# Sch.net
KiCad netlist of a schematic drawn in Altium Designer
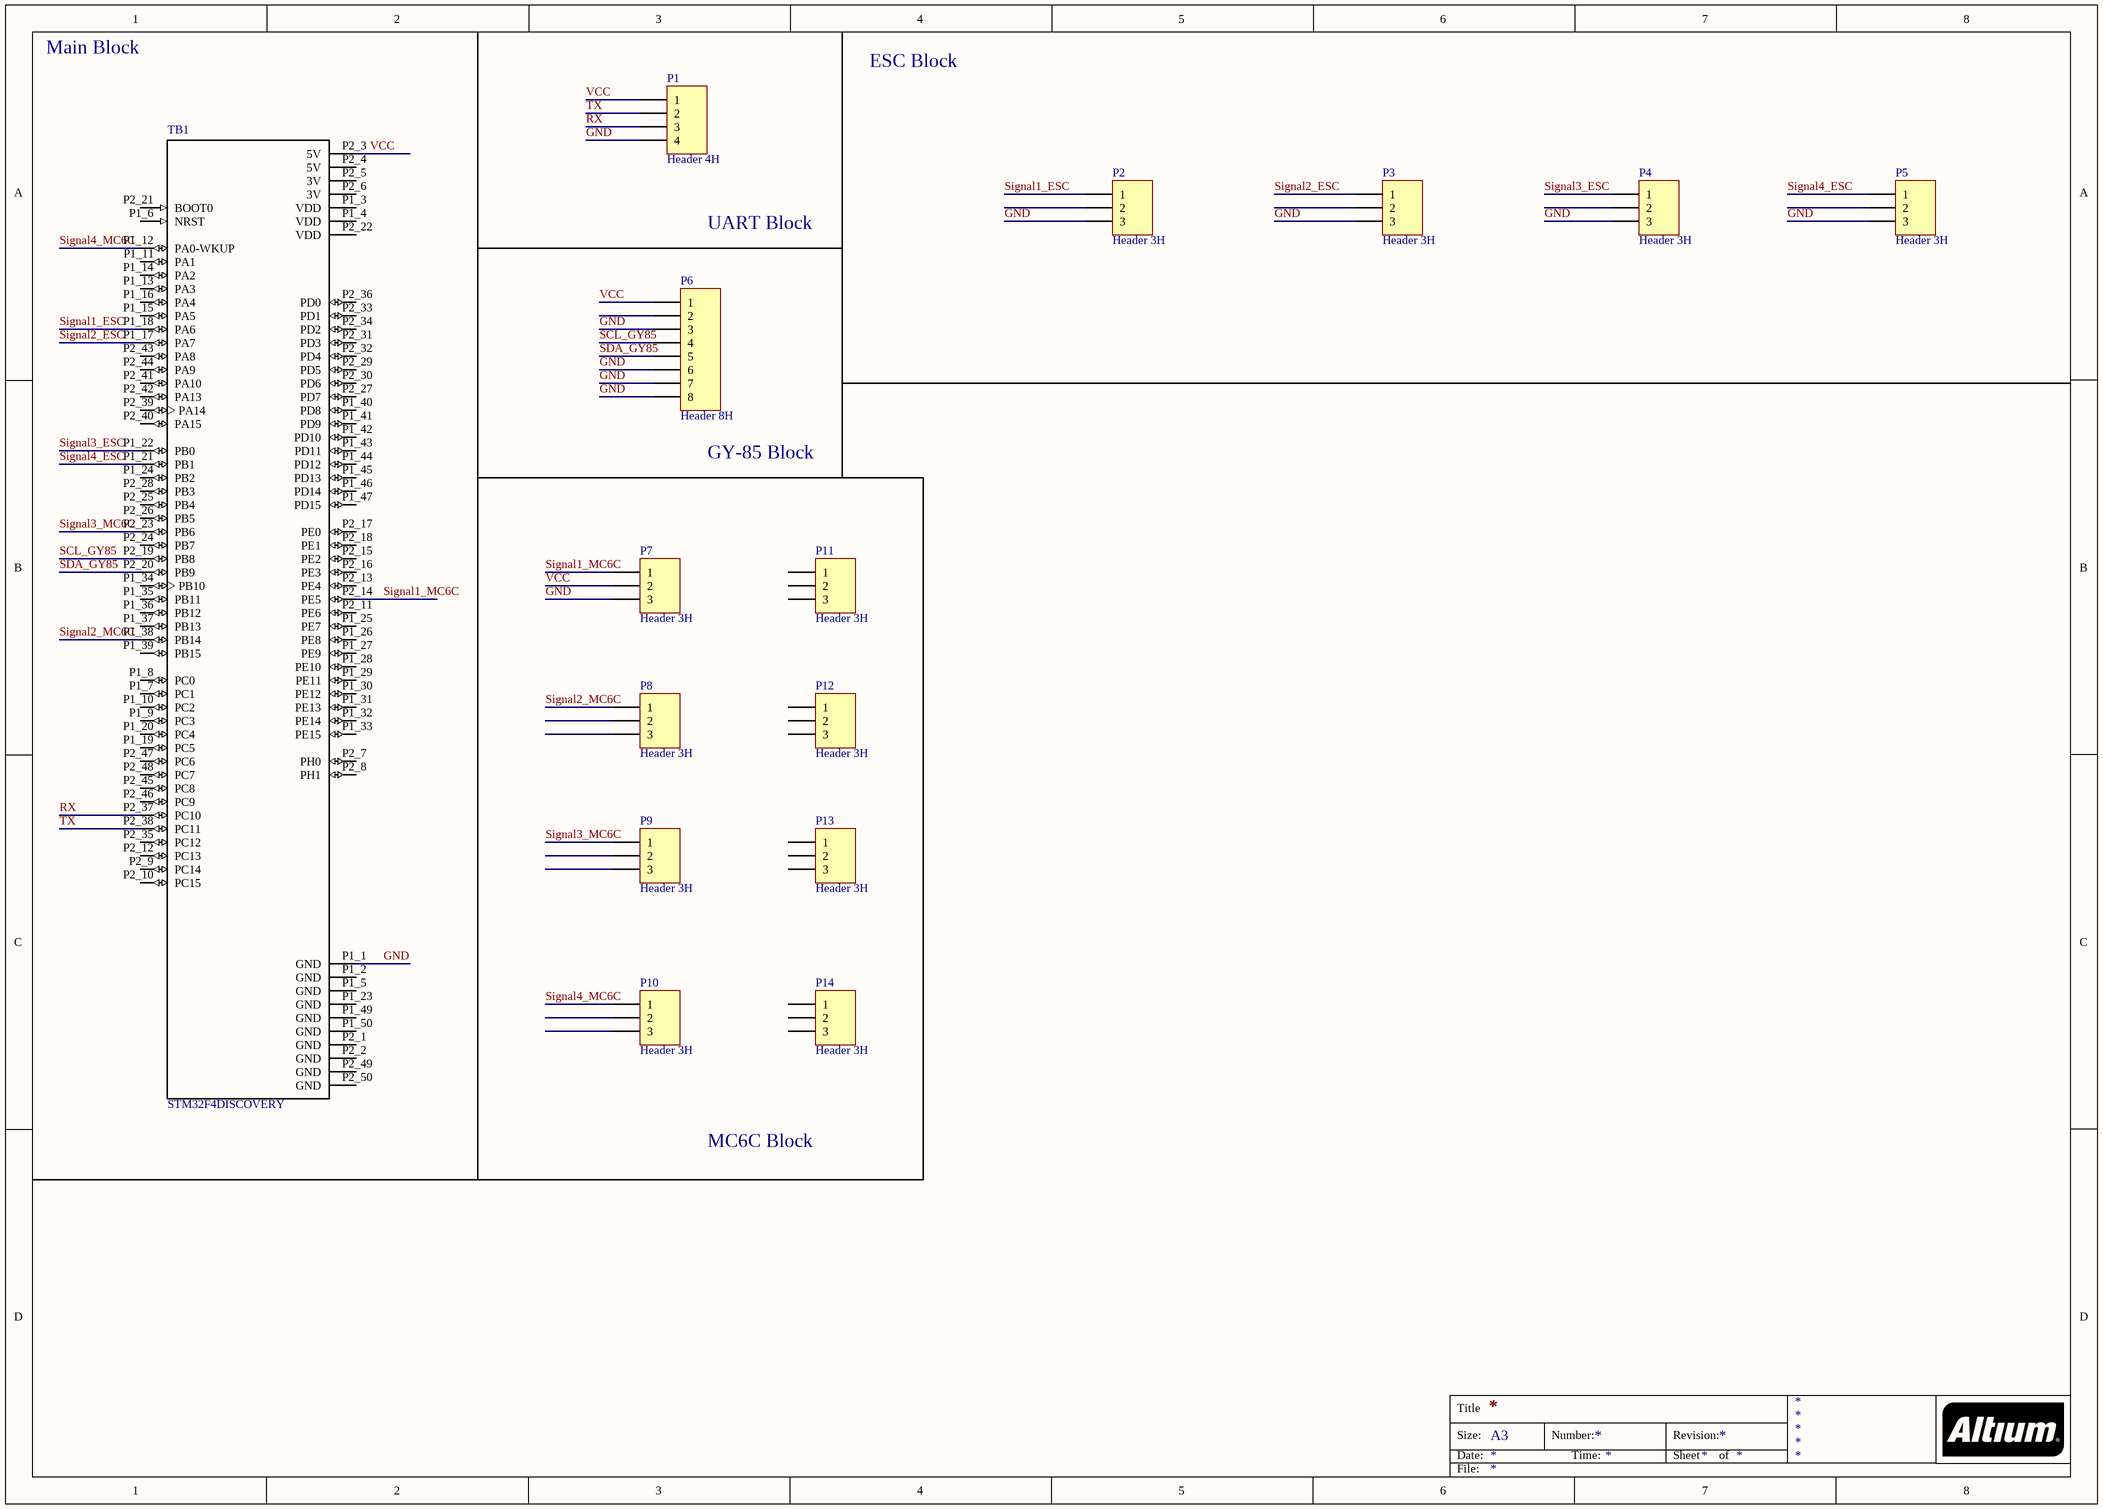
[diagram p0: Sch.SchDoc]

(export (version "E")
  (design (tool "Eeschema 10.0.6"))
  (components
    (comp (ref "P1")
      (value "Header 4H")
      (footprint "HDR1X4H")
      (description "Header, 4-Pin, Right Angle")
      (fields (field (name "PUBLISHER") "Altium Limited"))
      (libsource (lib "Miscellaneous Connectors") (part "Header 4H"))
    )
    (comp (ref "P2")
      (value "Header 3H")
      (footprint "HDR1X3H")
      (description "Header, 3-Pin, Right Angle")
      (fields (field (name "PUBLISHER") "Altium Limited"))
      (libsource (lib "Miscellaneous Connectors") (part "Header 3H"))
    )
    (comp (ref "P3")
      (value "Header 3H")
      (footprint "HDR1X3H")
      (description "Header, 3-Pin, Right Angle")
      (fields (field (name "PUBLISHER") "Altium Limited"))
      (libsource (lib "Miscellaneous Connectors") (part "Header 3H"))
    )
    (comp (ref "P4")
      (value "Header 3H")
      (footprint "HDR1X3H")
      (description "Header, 3-Pin, Right Angle")
      (fields (field (name "PUBLISHER") "Altium Limited"))
      (libsource (lib "Miscellaneous Connectors") (part "Header 3H"))
    )
    (comp (ref "P5")
      (value "Header 3H")
      (footprint "HDR1X3H")
      (description "Header, 3-Pin, Right Angle")
      (fields (field (name "PUBLISHER") "Altium Limited"))
      (libsource (lib "Miscellaneous Connectors") (part "Header 3H"))
    )
    (comp (ref "P6")
      (value "Header 8H")
      (footprint "HDR1X8H")
      (description "Header, 8-Pin, Right Angle")
      (fields (field (name "PUBLISHER") "Altium Limited"))
      (libsource (lib "Miscellaneous Connectors") (part "Header 8H"))
    )
    (comp (ref "P7")
      (value "Header 3H")
      (footprint "HDR1X3H")
      (description "Header, 3-Pin, Right Angle")
      (fields (field (name "PUBLISHER") "Altium Limited"))
      (libsource (lib "Miscellaneous Connectors") (part "Header 3H"))
    )
    (comp (ref "P8")
      (value "Header 3H")
      (footprint "HDR1X3H")
      (description "Header, 3-Pin, Right Angle")
      (fields (field (name "PUBLISHER") "Altium Limited"))
      (libsource (lib "Miscellaneous Connectors") (part "Header 3H"))
    )
    (comp (ref "P9")
      (value "Header 3H")
      (footprint "HDR1X3H")
      (description "Header, 3-Pin, Right Angle")
      (fields (field (name "PUBLISHER") "Altium Limited"))
      (libsource (lib "Miscellaneous Connectors") (part "Header 3H"))
    )
    (comp (ref "P10")
      (value "Header 3H")
      (footprint "HDR1X3H")
      (description "Header, 3-Pin, Right Angle")
      (fields (field (name "PUBLISHER") "Altium Limited"))
      (libsource (lib "Miscellaneous Connectors") (part "Header 3H"))
    )
    (comp (ref "P11")
      (value "Header 3H")
      (footprint "HDR1X3H")
      (description "Header, 3-Pin, Right Angle")
      (fields (field (name "PUBLISHER") "Altium Limited"))
      (libsource (lib "Miscellaneous Connectors") (part "Header 3H"))
    )
    (comp (ref "P12")
      (value "Header 3H")
      (footprint "HDR1X3H")
      (description "Header, 3-Pin, Right Angle")
      (fields (field (name "PUBLISHER") "Altium Limited"))
      (libsource (lib "Miscellaneous Connectors") (part "Header 3H"))
    )
    (comp (ref "P13")
      (value "Header 3H")
      (footprint "HDR1X3H")
      (description "Header, 3-Pin, Right Angle")
      (fields (field (name "PUBLISHER") "Altium Limited"))
      (libsource (lib "Miscellaneous Connectors") (part "Header 3H"))
    )
    (comp (ref "P14")
      (value "Header 3H")
      (footprint "HDR1X3H")
      (description "Header, 3-Pin, Right Angle")
      (fields (field (name "PUBLISHER") "Altium Limited"))
      (libsource (lib "Miscellaneous Connectors") (part "Header 3H"))
    )
    (comp (ref "TB1")
      (value "STM32F4DISCOVERY")
      (footprint "*MODULE_STM32F4DISCOVERY_STM32F4DISCOVERY(Primary)")
      (description "STM32F407VGT6 Discovery STM32F4 ARMÂ® CortexÂ®-M4 MCU 32-Bit Embedded Evaluation Board")
      (fields (field (name "MF") "STMicroelectronics"))
      (libsource (lib "STM32F4DISCOVERY") (part "STM32F4DISCOVERY"))
    )
  )
  (nets
    (net (code "1") (name "/GND") (class "Default")
      (node (ref "P1") (pin "4") (pinfunction "4_4") (pintype "passive"))
      (node (ref "P2") (pin "3") (pinfunction "3_3") (pintype "passive"))
      (node (ref "P3") (pin "3") (pinfunction "3_3") (pintype "passive"))
      (node (ref "P4") (pin "3") (pinfunction "3_3") (pintype "passive"))
      (node (ref "P5") (pin "3") (pinfunction "3_3") (pintype "passive"))
      (node (ref "P6") (pin "3") (pinfunction "3_3") (pintype "passive"))
      (node (ref "P6") (pin "6") (pinfunction "6_6") (pintype "passive"))
      (node (ref "P6") (pin "7") (pinfunction "7_7") (pintype "passive"))
      (node (ref "P6") (pin "8") (pinfunction "8_8") (pintype "passive"))
      (node (ref "P7") (pin "3") (pinfunction "3_3") (pintype "passive"))
      (node (ref "TB1") (pin "P1_1") (pinfunction "GND_P1_1") (pintype "power_in"))
    )
    (net (code "2") (name "/RX") (class "Default")
      (node (ref "P1") (pin "3") (pinfunction "3_3") (pintype "passive"))
      (node (ref "TB1") (pin "P2_37") (pinfunction "PC10_P2_37") (pintype "bidirectional"))
    )
    (net (code "3") (name "/SCL_GY85") (class "Default")
      (node (ref "P6") (pin "4") (pinfunction "4_4") (pintype "passive"))
      (node (ref "TB1") (pin "P2_19") (pinfunction "PB8_P2_19") (pintype "bidirectional"))
    )
    (net (code "4") (name "/SDA_GY85") (class "Default")
      (node (ref "P6") (pin "5") (pinfunction "5_5") (pintype "passive"))
      (node (ref "TB1") (pin "P2_20") (pinfunction "PB9_P2_20") (pintype "bidirectional"))
    )
    (net (code "5") (name "/Signal1_ESC") (class "Default")
      (node (ref "P2") (pin "1") (pinfunction "1_1") (pintype "passive"))
      (node (ref "TB1") (pin "P1_18") (pinfunction "PA6_P1_18") (pintype "bidirectional"))
    )
    (net (code "6") (name "/Signal1_MC6C") (class "Default")
      (node (ref "P7") (pin "1") (pinfunction "1_1") (pintype "passive"))
      (node (ref "TB1") (pin "P2_14") (pinfunction "PE5_P2_14") (pintype "bidirectional"))
    )
    (net (code "7") (name "/Signal2_ESC") (class "Default")
      (node (ref "P3") (pin "1") (pinfunction "1_1") (pintype "passive"))
      (node (ref "TB1") (pin "P1_17") (pinfunction "PA7_P1_17") (pintype "bidirectional"))
    )
    (net (code "8") (name "/Signal2_MC6C") (class "Default")
      (node (ref "P8") (pin "1") (pinfunction "1_1") (pintype "passive"))
      (node (ref "TB1") (pin "P1_38") (pinfunction "PB14_P1_38") (pintype "bidirectional"))
    )
    (net (code "9") (name "/Signal3_ESC") (class "Default")
      (node (ref "P4") (pin "1") (pinfunction "1_1") (pintype "passive"))
      (node (ref "TB1") (pin "P1_22") (pinfunction "PB0_P1_22") (pintype "bidirectional"))
    )
    (net (code "10") (name "/Signal3_MC6C") (class "Default")
      (node (ref "P9") (pin "1") (pinfunction "1_1") (pintype "passive"))
      (node (ref "TB1") (pin "P2_23") (pinfunction "PB6_P2_23") (pintype "bidirectional"))
    )
    (net (code "11") (name "/Signal4_ESC") (class "Default")
      (node (ref "P5") (pin "1") (pinfunction "1_1") (pintype "passive"))
      (node (ref "TB1") (pin "P1_21") (pinfunction "PB1_P1_21") (pintype "bidirectional"))
    )
    (net (code "12") (name "/Signal4_MC6C") (class "Default")
      (node (ref "P10") (pin "1") (pinfunction "1_1") (pintype "passive"))
      (node (ref "TB1") (pin "P1_12") (pinfunction "PA0-WKUP_P1_12") (pintype "bidirectional"))
    )
    (net (code "13") (name "/TX") (class "Default")
      (node (ref "P1") (pin "2") (pinfunction "2_2") (pintype "passive"))
      (node (ref "TB1") (pin "P2_38") (pinfunction "PC11_P2_38") (pintype "bidirectional"))
    )
    (net (code "14") (name "/VCC") (class "Default")
      (node (ref "P1") (pin "1") (pinfunction "1_1") (pintype "passive"))
      (node (ref "P6") (pin "1") (pinfunction "1_1") (pintype "passive"))
      (node (ref "P7") (pin "2") (pinfunction "2_2") (pintype "passive"))
      (node (ref "TB1") (pin "P2_3") (pinfunction "5V_P2_3") (pintype "power_in"))
    )
    (net (code "15") (name "unconnected-(P2-Pad2)") (class "Default")
      (node (ref "P2") (pin "2") (pinfunction "2_2") (pintype "passive"))
    )
    (net (code "16") (name "unconnected-(P3-Pad2)") (class "Default")
      (node (ref "P3") (pin "2") (pinfunction "2_2") (pintype "passive"))
    )
    (net (code "17") (name "unconnected-(P4-Pad2)") (class "Default")
      (node (ref "P4") (pin "2") (pinfunction "2_2") (pintype "passive"))
    )
    (net (code "18") (name "unconnected-(P5-Pad2)") (class "Default")
      (node (ref "P5") (pin "2") (pinfunction "2_2") (pintype "passive"))
    )
    (net (code "19") (name "unconnected-(P6-Pad2)") (class "Default")
      (node (ref "P6") (pin "2") (pinfunction "2_2") (pintype "passive"))
    )
    (net (code "20") (name "unconnected-(P8-Pad2)") (class "Default")
      (node (ref "P8") (pin "2") (pinfunction "2_2") (pintype "passive"))
    )
    (net (code "21") (name "unconnected-(P8-Pad3)") (class "Default")
      (node (ref "P8") (pin "3") (pinfunction "3_3") (pintype "passive"))
    )
    (net (code "22") (name "unconnected-(P9-Pad2)") (class "Default")
      (node (ref "P9") (pin "2") (pinfunction "2_2") (pintype "passive"))
    )
    (net (code "23") (name "unconnected-(P9-Pad3)") (class "Default")
      (node (ref "P9") (pin "3") (pinfunction "3_3") (pintype "passive"))
    )
    (net (code "24") (name "unconnected-(P10-Pad2)") (class "Default")
      (node (ref "P10") (pin "2") (pinfunction "2_2") (pintype "passive"))
    )
    (net (code "25") (name "unconnected-(P10-Pad3)") (class "Default")
      (node (ref "P10") (pin "3") (pinfunction "3_3") (pintype "passive"))
    )
    (net (code "26") (name "unconnected-(P11-Pad1)") (class "Default")
      (node (ref "P11") (pin "1") (pinfunction "1_1") (pintype "passive"))
    )
    (net (code "27") (name "unconnected-(P11-Pad2)") (class "Default")
      (node (ref "P11") (pin "2") (pinfunction "2_2") (pintype "passive"))
    )
    (net (code "28") (name "unconnected-(P11-Pad3)") (class "Default")
      (node (ref "P11") (pin "3") (pinfunction "3_3") (pintype "passive"))
    )
    (net (code "29") (name "unconnected-(P12-Pad1)") (class "Default")
      (node (ref "P12") (pin "1") (pinfunction "1_1") (pintype "passive"))
    )
    (net (code "30") (name "unconnected-(P12-Pad2)") (class "Default")
      (node (ref "P12") (pin "2") (pinfunction "2_2") (pintype "passive"))
    )
    (net (code "31") (name "unconnected-(P12-Pad3)") (class "Default")
      (node (ref "P12") (pin "3") (pinfunction "3_3") (pintype "passive"))
    )
    (net (code "32") (name "unconnected-(P13-Pad1)") (class "Default")
      (node (ref "P13") (pin "1") (pinfunction "1_1") (pintype "passive"))
    )
    (net (code "33") (name "unconnected-(P13-Pad2)") (class "Default")
      (node (ref "P13") (pin "2") (pinfunction "2_2") (pintype "passive"))
    )
    (net (code "34") (name "unconnected-(P13-Pad3)") (class "Default")
      (node (ref "P13") (pin "3") (pinfunction "3_3") (pintype "passive"))
    )
    (net (code "35") (name "unconnected-(P14-Pad1)") (class "Default")
      (node (ref "P14") (pin "1") (pinfunction "1_1") (pintype "passive"))
    )
    (net (code "36") (name "unconnected-(P14-Pad2)") (class "Default")
      (node (ref "P14") (pin "2") (pinfunction "2_2") (pintype "passive"))
    )
    (net (code "37") (name "unconnected-(P14-Pad3)") (class "Default")
      (node (ref "P14") (pin "3") (pinfunction "3_3") (pintype "passive"))
    )
    (net (code "38") (name "unconnected-(TB1-3V-PadP2_5)") (class "Default")
      (node (ref "TB1") (pin "P2_5") (pinfunction "3V_P2_5") (pintype "power_in"))
    )
    (net (code "39") (name "unconnected-(TB1-3V-PadP2_6)") (class "Default")
      (node (ref "TB1") (pin "P2_6") (pinfunction "3V_P2_6") (pintype "power_in"))
    )
    (net (code "40") (name "unconnected-(TB1-5V-PadP2_4)") (class "Default")
      (node (ref "TB1") (pin "P2_4") (pinfunction "5V_P2_4") (pintype "power_in"))
    )
    (net (code "41") (name "unconnected-(TB1-BOOT0-PadP2_21)") (class "Default")
      (node (ref "TB1") (pin "P2_21") (pinfunction "BOOT0_P2_21") (pintype "input"))
    )
    (net (code "42") (name "unconnected-(TB1-GND-PadP1_2)") (class "Default")
      (node (ref "TB1") (pin "P1_2") (pinfunction "GND_P1_2") (pintype "power_in"))
    )
    (net (code "43") (name "unconnected-(TB1-GND-PadP1_5)") (class "Default")
      (node (ref "TB1") (pin "P1_5") (pinfunction "GND_P1_5") (pintype "power_in"))
    )
    (net (code "44") (name "unconnected-(TB1-GND-PadP1_23)") (class "Default")
      (node (ref "TB1") (pin "P1_23") (pinfunction "GND_P1_23") (pintype "power_in"))
    )
    (net (code "45") (name "unconnected-(TB1-GND-PadP1_49)") (class "Default")
      (node (ref "TB1") (pin "P1_49") (pinfunction "GND_P1_49") (pintype "power_in"))
    )
    (net (code "46") (name "unconnected-(TB1-GND-PadP1_50)") (class "Default")
      (node (ref "TB1") (pin "P1_50") (pinfunction "GND_P1_50") (pintype "power_in"))
    )
    (net (code "47") (name "unconnected-(TB1-GND-PadP2_1)") (class "Default")
      (node (ref "TB1") (pin "P2_1") (pinfunction "GND_P2_1") (pintype "power_in"))
    )
    (net (code "48") (name "unconnected-(TB1-GND-PadP2_2)") (class "Default")
      (node (ref "TB1") (pin "P2_2") (pinfunction "GND_P2_2") (pintype "power_in"))
    )
    (net (code "49") (name "unconnected-(TB1-GND-PadP2_49)") (class "Default")
      (node (ref "TB1") (pin "P2_49") (pinfunction "GND_P2_49") (pintype "power_in"))
    )
    (net (code "50") (name "unconnected-(TB1-GND-PadP2_50)") (class "Default")
      (node (ref "TB1") (pin "P2_50") (pinfunction "GND_P2_50") (pintype "power_in"))
    )
    (net (code "51") (name "unconnected-(TB1-NRST-PadP1_6)") (class "Default")
      (node (ref "TB1") (pin "P1_6") (pinfunction "NRST_P1_6") (pintype "input"))
    )
    (net (code "52") (name "unconnected-(TB1-PA1-PadP1_11)") (class "Default")
      (node (ref "TB1") (pin "P1_11") (pinfunction "PA1_P1_11") (pintype "bidirectional"))
    )
    (net (code "53") (name "unconnected-(TB1-PA2-PadP1_14)") (class "Default")
      (node (ref "TB1") (pin "P1_14") (pinfunction "PA2_P1_14") (pintype "bidirectional"))
    )
    (net (code "54") (name "unconnected-(TB1-PA3-PadP1_13)") (class "Default")
      (node (ref "TB1") (pin "P1_13") (pinfunction "PA3_P1_13") (pintype "bidirectional"))
    )
    (net (code "55") (name "unconnected-(TB1-PA4-PadP1_16)") (class "Default")
      (node (ref "TB1") (pin "P1_16") (pinfunction "PA4_P1_16") (pintype "bidirectional"))
    )
    (net (code "56") (name "unconnected-(TB1-PA5-PadP1_15)") (class "Default")
      (node (ref "TB1") (pin "P1_15") (pinfunction "PA5_P1_15") (pintype "bidirectional"))
    )
    (net (code "57") (name "unconnected-(TB1-PA8-PadP2_43)") (class "Default")
      (node (ref "TB1") (pin "P2_43") (pinfunction "PA8_P2_43") (pintype "bidirectional"))
    )
    (net (code "58") (name "unconnected-(TB1-PA9-PadP2_44)") (class "Default")
      (node (ref "TB1") (pin "P2_44") (pinfunction "PA9_P2_44") (pintype "bidirectional"))
    )
    (net (code "59") (name "unconnected-(TB1-PA10-PadP2_41)") (class "Default")
      (node (ref "TB1") (pin "P2_41") (pinfunction "PA10_P2_41") (pintype "bidirectional"))
    )
    (net (code "60") (name "unconnected-(TB1-PA13-PadP2_42)") (class "Default")
      (node (ref "TB1") (pin "P2_42") (pinfunction "PA13_P2_42") (pintype "bidirectional"))
    )
    (net (code "61") (name "unconnected-(TB1-PA14-PadP2_39)") (class "Default")
      (node (ref "TB1") (pin "P2_39") (pinfunction "PA14_P2_39") (pintype "bidirectional"))
    )
    (net (code "62") (name "unconnected-(TB1-PA15-PadP2_40)") (class "Default")
      (node (ref "TB1") (pin "P2_40") (pinfunction "PA15_P2_40") (pintype "bidirectional"))
    )
    (net (code "63") (name "unconnected-(TB1-PB2-PadP1_24)") (class "Default")
      (node (ref "TB1") (pin "P1_24") (pinfunction "PB2_P1_24") (pintype "bidirectional"))
    )
    (net (code "64") (name "unconnected-(TB1-PB3-PadP2_28)") (class "Default")
      (node (ref "TB1") (pin "P2_28") (pinfunction "PB3_P2_28") (pintype "bidirectional"))
    )
    (net (code "65") (name "unconnected-(TB1-PB4-PadP2_25)") (class "Default")
      (node (ref "TB1") (pin "P2_25") (pinfunction "PB4_P2_25") (pintype "bidirectional"))
    )
    (net (code "66") (name "unconnected-(TB1-PB5-PadP2_26)") (class "Default")
      (node (ref "TB1") (pin "P2_26") (pinfunction "PB5_P2_26") (pintype "bidirectional"))
    )
    (net (code "67") (name "unconnected-(TB1-PB7-PadP2_24)") (class "Default")
      (node (ref "TB1") (pin "P2_24") (pinfunction "PB7_P2_24") (pintype "bidirectional"))
    )
    (net (code "68") (name "unconnected-(TB1-PB10-PadP1_34)") (class "Default")
      (node (ref "TB1") (pin "P1_34") (pinfunction "PB10_P1_34") (pintype "bidirectional"))
    )
    (net (code "69") (name "unconnected-(TB1-PB11-PadP1_35)") (class "Default")
      (node (ref "TB1") (pin "P1_35") (pinfunction "PB11_P1_35") (pintype "bidirectional"))
    )
    (net (code "70") (name "unconnected-(TB1-PB12-PadP1_36)") (class "Default")
      (node (ref "TB1") (pin "P1_36") (pinfunction "PB12_P1_36") (pintype "bidirectional"))
    )
    (net (code "71") (name "unconnected-(TB1-PB13-PadP1_37)") (class "Default")
      (node (ref "TB1") (pin "P1_37") (pinfunction "PB13_P1_37") (pintype "bidirectional"))
    )
    (net (code "72") (name "unconnected-(TB1-PB15-PadP1_39)") (class "Default")
      (node (ref "TB1") (pin "P1_39") (pinfunction "PB15_P1_39") (pintype "bidirectional"))
    )
    (net (code "73") (name "unconnected-(TB1-PC0-PadP1_8)") (class "Default")
      (node (ref "TB1") (pin "P1_8") (pinfunction "PC0_P1_8") (pintype "bidirectional"))
    )
    (net (code "74") (name "unconnected-(TB1-PC1-PadP1_7)") (class "Default")
      (node (ref "TB1") (pin "P1_7") (pinfunction "PC1_P1_7") (pintype "bidirectional"))
    )
    (net (code "75") (name "unconnected-(TB1-PC2-PadP1_10)") (class "Default")
      (node (ref "TB1") (pin "P1_10") (pinfunction "PC2_P1_10") (pintype "bidirectional"))
    )
    (net (code "76") (name "unconnected-(TB1-PC3-PadP1_9)") (class "Default")
      (node (ref "TB1") (pin "P1_9") (pinfunction "PC3_P1_9") (pintype "bidirectional"))
    )
    (net (code "77") (name "unconnected-(TB1-PC4-PadP1_20)") (class "Default")
      (node (ref "TB1") (pin "P1_20") (pinfunction "PC4_P1_20") (pintype "bidirectional"))
    )
    (net (code "78") (name "unconnected-(TB1-PC5-PadP1_19)") (class "Default")
      (node (ref "TB1") (pin "P1_19") (pinfunction "PC5_P1_19") (pintype "bidirectional"))
    )
    (net (code "79") (name "unconnected-(TB1-PC6-PadP2_47)") (class "Default")
      (node (ref "TB1") (pin "P2_47") (pinfunction "PC6_P2_47") (pintype "bidirectional"))
    )
    (net (code "80") (name "unconnected-(TB1-PC7-PadP2_48)") (class "Default")
      (node (ref "TB1") (pin "P2_48") (pinfunction "PC7_P2_48") (pintype "bidirectional"))
    )
    (net (code "81") (name "unconnected-(TB1-PC8-PadP2_45)") (class "Default")
      (node (ref "TB1") (pin "P2_45") (pinfunction "PC8_P2_45") (pintype "bidirectional"))
    )
    (net (code "82") (name "unconnected-(TB1-PC9-PadP2_46)") (class "Default")
      (node (ref "TB1") (pin "P2_46") (pinfunction "PC9_P2_46") (pintype "bidirectional"))
    )
    (net (code "83") (name "unconnected-(TB1-PC12-PadP2_35)") (class "Default")
      (node (ref "TB1") (pin "P2_35") (pinfunction "PC12_P2_35") (pintype "bidirectional"))
    )
    (net (code "84") (name "unconnected-(TB1-PC13-PadP2_12)") (class "Default")
      (node (ref "TB1") (pin "P2_12") (pinfunction "PC13_P2_12") (pintype "bidirectional"))
    )
    (net (code "85") (name "unconnected-(TB1-PC14-PadP2_9)") (class "Default")
      (node (ref "TB1") (pin "P2_9") (pinfunction "PC14_P2_9") (pintype "bidirectional"))
    )
    (net (code "86") (name "unconnected-(TB1-PC15-PadP2_10)") (class "Default")
      (node (ref "TB1") (pin "P2_10") (pinfunction "PC15_P2_10") (pintype "bidirectional"))
    )
    (net (code "87") (name "unconnected-(TB1-PD0-PadP2_36)") (class "Default")
      (node (ref "TB1") (pin "P2_36") (pinfunction "PD0_P2_36") (pintype "bidirectional"))
    )
    (net (code "88") (name "unconnected-(TB1-PD1-PadP2_33)") (class "Default")
      (node (ref "TB1") (pin "P2_33") (pinfunction "PD1_P2_33") (pintype "bidirectional"))
    )
    (net (code "89") (name "unconnected-(TB1-PD2-PadP2_34)") (class "Default")
      (node (ref "TB1") (pin "P2_34") (pinfunction "PD2_P2_34") (pintype "bidirectional"))
    )
    (net (code "90") (name "unconnected-(TB1-PD3-PadP2_31)") (class "Default")
      (node (ref "TB1") (pin "P2_31") (pinfunction "PD3_P2_31") (pintype "bidirectional"))
    )
    (net (code "91") (name "unconnected-(TB1-PD4-PadP2_32)") (class "Default")
      (node (ref "TB1") (pin "P2_32") (pinfunction "PD4_P2_32") (pintype "bidirectional"))
    )
    (net (code "92") (name "unconnected-(TB1-PD5-PadP2_29)") (class "Default")
      (node (ref "TB1") (pin "P2_29") (pinfunction "PD5_P2_29") (pintype "bidirectional"))
    )
    (net (code "93") (name "unconnected-(TB1-PD6-PadP2_30)") (class "Default")
      (node (ref "TB1") (pin "P2_30") (pinfunction "PD6_P2_30") (pintype "bidirectional"))
    )
    (net (code "94") (name "unconnected-(TB1-PD7-PadP2_27)") (class "Default")
      (node (ref "TB1") (pin "P2_27") (pinfunction "PD7_P2_27") (pintype "bidirectional"))
    )
    (net (code "95") (name "unconnected-(TB1-PD8-PadP1_40)") (class "Default")
      (node (ref "TB1") (pin "P1_40") (pinfunction "PD8_P1_40") (pintype "bidirectional"))
    )
    (net (code "96") (name "unconnected-(TB1-PD9-PadP1_41)") (class "Default")
      (node (ref "TB1") (pin "P1_41") (pinfunction "PD9_P1_41") (pintype "bidirectional"))
    )
    (net (code "97") (name "unconnected-(TB1-PD10-PadP1_42)") (class "Default")
      (node (ref "TB1") (pin "P1_42") (pinfunction "PD10_P1_42") (pintype "bidirectional"))
    )
    (net (code "98") (name "unconnected-(TB1-PD11-PadP1_43)") (class "Default")
      (node (ref "TB1") (pin "P1_43") (pinfunction "PD11_P1_43") (pintype "bidirectional"))
    )
    (net (code "99") (name "unconnected-(TB1-PD12-PadP1_44)") (class "Default")
      (node (ref "TB1") (pin "P1_44") (pinfunction "PD12_P1_44") (pintype "bidirectional"))
    )
    (net (code "100") (name "unconnected-(TB1-PD13-PadP1_45)") (class "Default")
      (node (ref "TB1") (pin "P1_45") (pinfunction "PD13_P1_45") (pintype "bidirectional"))
    )
    (net (code "101") (name "unconnected-(TB1-PD14-PadP1_46)") (class "Default")
      (node (ref "TB1") (pin "P1_46") (pinfunction "PD14_P1_46") (pintype "bidirectional"))
    )
    (net (code "102") (name "unconnected-(TB1-PD15-PadP1_47)") (class "Default")
      (node (ref "TB1") (pin "P1_47") (pinfunction "PD15_P1_47") (pintype "bidirectional"))
    )
    (net (code "103") (name "unconnected-(TB1-PE0-PadP2_17)") (class "Default")
      (node (ref "TB1") (pin "P2_17") (pinfunction "PE0_P2_17") (pintype "bidirectional"))
    )
    (net (code "104") (name "unconnected-(TB1-PE1-PadP2_18)") (class "Default")
      (node (ref "TB1") (pin "P2_18") (pinfunction "PE1_P2_18") (pintype "bidirectional"))
    )
    (net (code "105") (name "unconnected-(TB1-PE2-PadP2_15)") (class "Default")
      (node (ref "TB1") (pin "P2_15") (pinfunction "PE2_P2_15") (pintype "bidirectional"))
    )
    (net (code "106") (name "unconnected-(TB1-PE3-PadP2_16)") (class "Default")
      (node (ref "TB1") (pin "P2_16") (pinfunction "PE3_P2_16") (pintype "bidirectional"))
    )
    (net (code "107") (name "unconnected-(TB1-PE4-PadP2_13)") (class "Default")
      (node (ref "TB1") (pin "P2_13") (pinfunction "PE4_P2_13") (pintype "bidirectional"))
    )
    (net (code "108") (name "unconnected-(TB1-PE6-PadP2_11)") (class "Default")
      (node (ref "TB1") (pin "P2_11") (pinfunction "PE6_P2_11") (pintype "bidirectional"))
    )
    (net (code "109") (name "unconnected-(TB1-PE7-PadP1_25)") (class "Default")
      (node (ref "TB1") (pin "P1_25") (pinfunction "PE7_P1_25") (pintype "bidirectional"))
    )
    (net (code "110") (name "unconnected-(TB1-PE8-PadP1_26)") (class "Default")
      (node (ref "TB1") (pin "P1_26") (pinfunction "PE8_P1_26") (pintype "bidirectional"))
    )
    (net (code "111") (name "unconnected-(TB1-PE9-PadP1_27)") (class "Default")
      (node (ref "TB1") (pin "P1_27") (pinfunction "PE9_P1_27") (pintype "bidirectional"))
    )
    (net (code "112") (name "unconnected-(TB1-PE10-PadP1_28)") (class "Default")
      (node (ref "TB1") (pin "P1_28") (pinfunction "PE10_P1_28") (pintype "bidirectional"))
    )
    (net (code "113") (name "unconnected-(TB1-PE11-PadP1_29)") (class "Default")
      (node (ref "TB1") (pin "P1_29") (pinfunction "PE11_P1_29") (pintype "bidirectional"))
    )
    (net (code "114") (name "unconnected-(TB1-PE12-PadP1_30)") (class "Default")
      (node (ref "TB1") (pin "P1_30") (pinfunction "PE12_P1_30") (pintype "bidirectional"))
    )
    (net (code "115") (name "unconnected-(TB1-PE13-PadP1_31)") (class "Default")
      (node (ref "TB1") (pin "P1_31") (pinfunction "PE13_P1_31") (pintype "bidirectional"))
    )
    (net (code "116") (name "unconnected-(TB1-PE14-PadP1_32)") (class "Default")
      (node (ref "TB1") (pin "P1_32") (pinfunction "PE14_P1_32") (pintype "bidirectional"))
    )
    (net (code "117") (name "unconnected-(TB1-PE15-PadP1_33)") (class "Default")
      (node (ref "TB1") (pin "P1_33") (pinfunction "PE15_P1_33") (pintype "bidirectional"))
    )
    (net (code "118") (name "unconnected-(TB1-PH0-PadP2_7)") (class "Default")
      (node (ref "TB1") (pin "P2_7") (pinfunction "PH0_P2_7") (pintype "bidirectional"))
    )
    (net (code "119") (name "unconnected-(TB1-PH1-PadP2_8)") (class "Default")
      (node (ref "TB1") (pin "P2_8") (pinfunction "PH1_P2_8") (pintype "bidirectional"))
    )
    (net (code "120") (name "unconnected-(TB1-VDD-PadP1_3)") (class "Default")
      (node (ref "TB1") (pin "P1_3") (pinfunction "VDD_P1_3") (pintype "power_in"))
    )
    (net (code "121") (name "unconnected-(TB1-VDD-PadP1_4)") (class "Default")
      (node (ref "TB1") (pin "P1_4") (pinfunction "VDD_P1_4") (pintype "power_in"))
    )
    (net (code "122") (name "unconnected-(TB1-VDD-PadP2_22)") (class "Default")
      (node (ref "TB1") (pin "P2_22") (pinfunction "VDD_P2_22") (pintype "power_in"))
    )
  )
)
